# powermeter.net
KiCad netlist of a schematic drawn in EAGLE
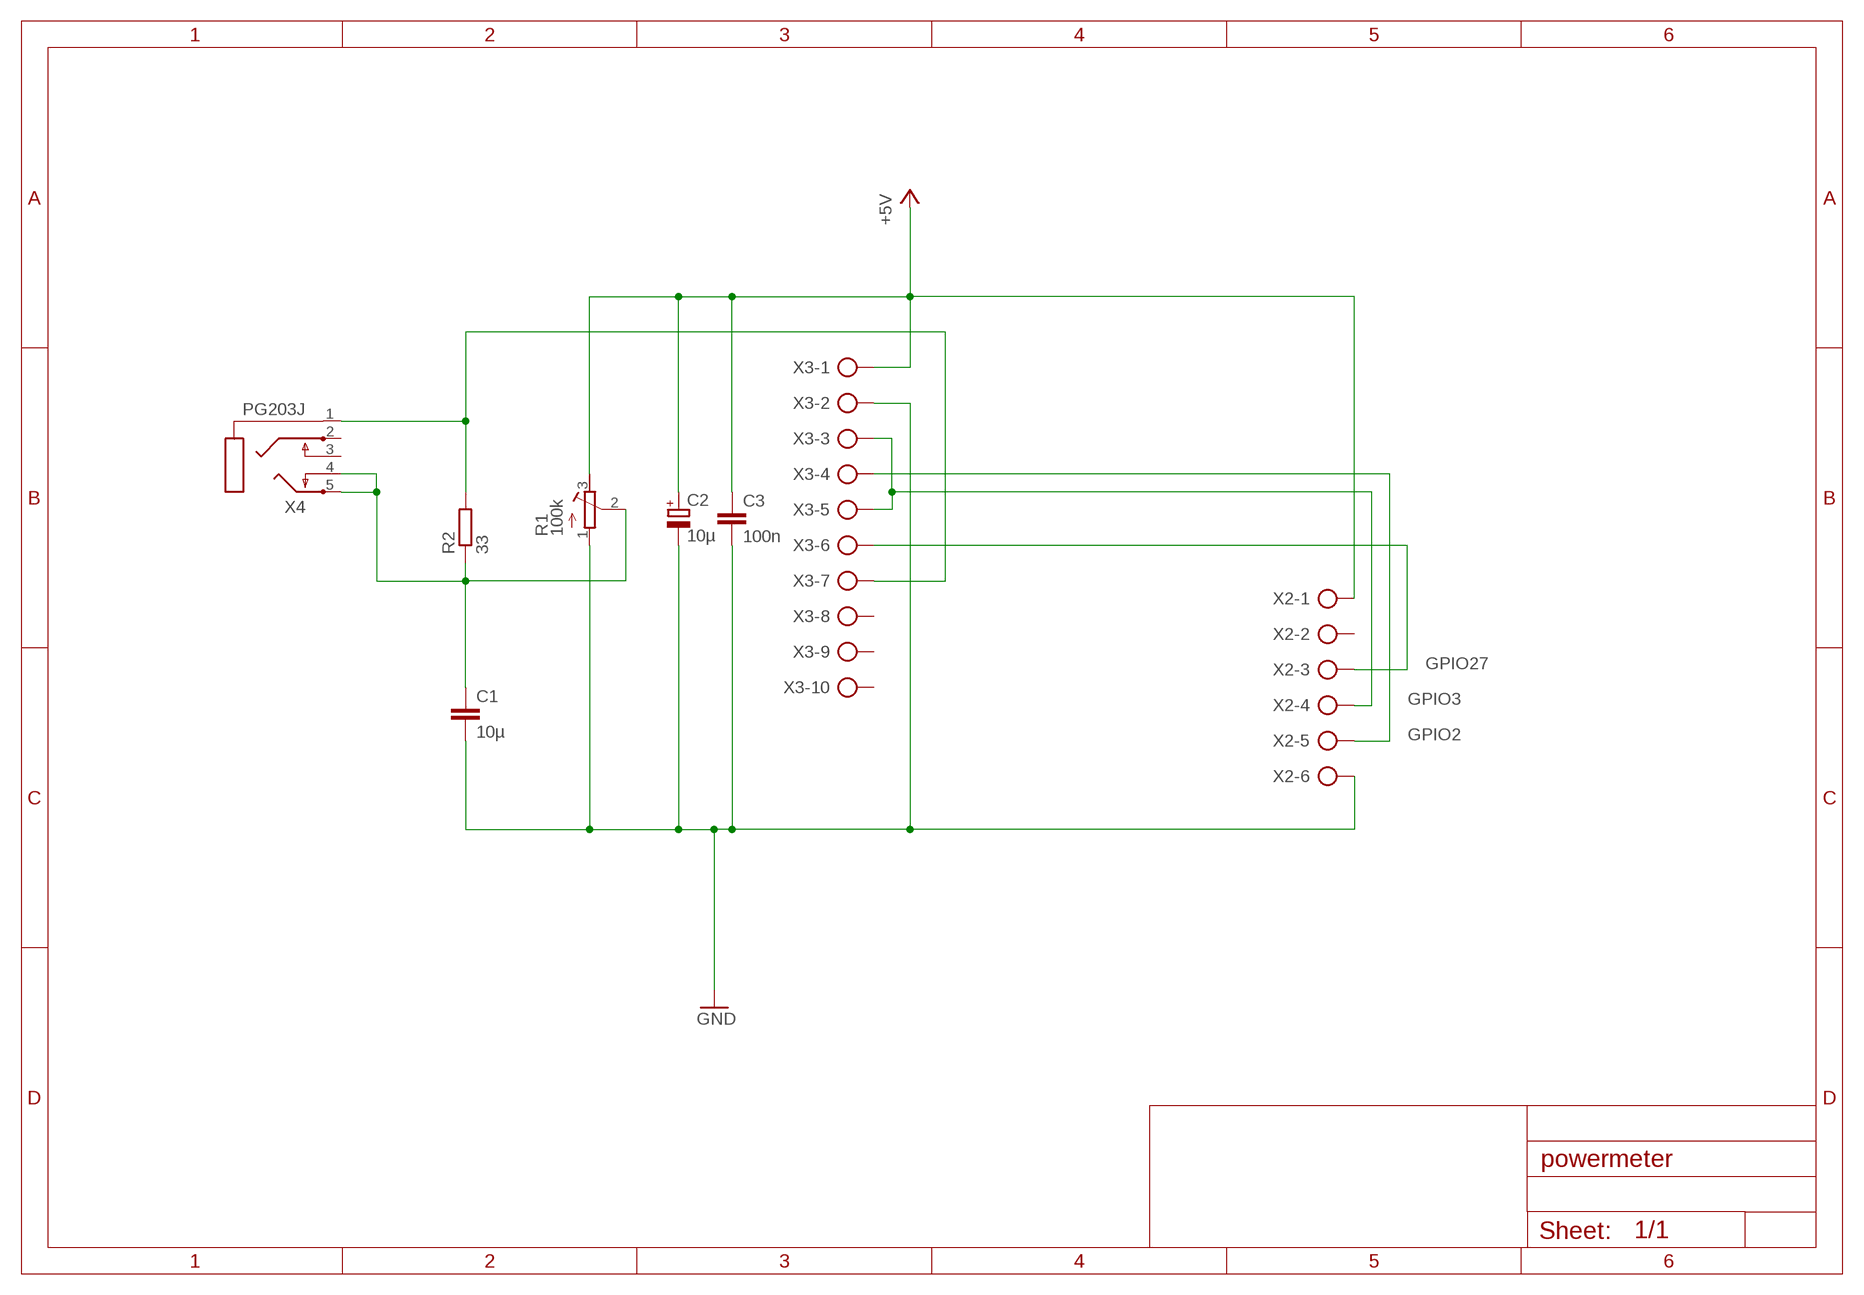
[diagram p0: schematic, sheet 1]

(export (version "E")
  (design (tool "Eeschema 10.0.6"))
  (components
    (comp (ref "C1")
      (value "10µ")
      (footprint "eagle-import:C050-025X075")
      (libsource (lib "eagle-import") (part "C-EU050-025X075"))
    )
    (comp (ref "C2")
      (value "10µ")
      (footprint "eagle-import:E5-10,5")
      (libsource (lib "eagle-import") (part "CPOL-EUE5-10.5"))
    )
    (comp (ref "C3")
      (value "100n")
      (footprint "eagle-import:C050-025X075")
      (libsource (lib "eagle-import") (part "C-EU050-025X075"))
    )
    (comp (ref "R1")
      (value "100k")
      (footprint "eagle-import:RTRIM64W")
      (libsource (lib "eagle-import") (part "R-TRIMM64W"))
    )
    (comp (ref "R2")
      (value "33")
      (footprint "eagle-import:0309_12")
      (libsource (lib "eagle-import") (part "R-EU_0309/12"))
    )
    (comp (ref "X2")
      (value "AK300/6")
      (footprint "eagle-import:AK300_6")
      (libsource (lib "eagle-import") (part "AK300/6"))
    )
    (comp (ref "X3")
      (value "AK300/10")
      (footprint "eagle-import:AK300_10")
      (libsource (lib "eagle-import") (part "AK300/10"))
    )
    (comp (ref "X4")
      (value "PG203J")
      (footprint "eagle-import:PG203J")
      (libsource (lib "eagle-import") (part "PG203J"))
    )
  )
  (nets
    (net (code "1") (name "+5V") (class "Default")
      (node (ref "C2") (pin "+") (pinfunction "+_+") (pintype "passive"))
      (node (ref "C3") (pin "1") (pinfunction "1_1") (pintype "passive"))
      (node (ref "R1") (pin "3") (pinfunction "E_3") (pintype "passive"))
      (node (ref "X2") (pin "1") (pinfunction "KL_1") (pintype "passive"))
      (node (ref "X3") (pin "1") (pinfunction "KL_1") (pintype "passive"))
    )
    (net (code "2") (name "/GPIO2") (class "Default")
      (node (ref "X2") (pin "5") (pinfunction "KL_5") (pintype "passive"))
      (node (ref "X3") (pin "4") (pinfunction "KL_4") (pintype "passive"))
    )
    (net (code "3") (name "/GPIO3") (class "Default")
      (node (ref "X2") (pin "4") (pinfunction "KL_4") (pintype "passive"))
      (node (ref "X3") (pin "3") (pinfunction "KL_3") (pintype "passive"))
      (node (ref "X3") (pin "5") (pinfunction "KL_5") (pintype "passive"))
    )
    (net (code "4") (name "/GPIO27") (class "Default")
      (node (ref "X2") (pin "3") (pinfunction "KL_3") (pintype "passive"))
      (node (ref "X3") (pin "6") (pinfunction "KL_6") (pintype "passive"))
    )
    (net (code "5") (name "GND") (class "Default")
      (node (ref "C1") (pin "2") (pinfunction "2_2") (pintype "passive"))
      (node (ref "C2") (pin "-") (pinfunction "-_-") (pintype "passive"))
      (node (ref "C3") (pin "2") (pinfunction "2_2") (pintype "passive"))
      (node (ref "R1") (pin "1") (pinfunction "A_1") (pintype "passive"))
      (node (ref "X2") (pin "6") (pinfunction "KL_6") (pintype "passive"))
      (node (ref "X3") (pin "2") (pinfunction "KL_2") (pintype "passive"))
    )
    (net (code "6") (name "Net-(R1-S)") (class "Default")
      (node (ref "C1") (pin "1") (pinfunction "1_1") (pintype "passive"))
      (node (ref "R1") (pin "2") (pinfunction "S_2") (pintype "passive"))
      (node (ref "R2") (pin "1") (pinfunction "1_1") (pintype "passive"))
      (node (ref "X4") (pin "4") (pinfunction "4_4") (pintype "passive"))
      (node (ref "X4") (pin "5") (pinfunction "5_5") (pintype "passive"))
    )
    (net (code "7") (name "Net-(X3H-KL)") (class "Default")
      (node (ref "R2") (pin "2") (pinfunction "2_2") (pintype "passive"))
      (node (ref "X3") (pin "7") (pinfunction "KL_7") (pintype "passive"))
      (node (ref "X4") (pin "1") (pinfunction "1_1") (pintype "passive"))
    )
    (net (code "8") (name "unconnected-(X2B-KL-Pad2)") (class "Default")
      (node (ref "X2") (pin "2") (pinfunction "KL_2") (pintype "passive"))
    )
    (net (code "9") (name "unconnected-(X3B-KL-Pad10)") (class "Default")
      (node (ref "X3") (pin "10") (pinfunction "KL_10") (pintype "passive"))
    )
    (net (code "10") (name "unconnected-(X3I-KL-Pad8)") (class "Default")
      (node (ref "X3") (pin "8") (pinfunction "KL_8") (pintype "passive"))
    )
    (net (code "11") (name "unconnected-(X3J-KL-Pad9)") (class "Default")
      (node (ref "X3") (pin "9") (pinfunction "KL_9") (pintype "passive"))
    )
    (net (code "12") (name "unconnected-(X4-Pad2)") (class "Default")
      (node (ref "X4") (pin "2") (pinfunction "2_2") (pintype "passive"))
    )
    (net (code "13") (name "unconnected-(X4-Pad3)") (class "Default")
      (node (ref "X4") (pin "3") (pinfunction "3_3") (pintype "passive"))
    )
  )
)
